# BackplaneConnector.net
KiCad netlist of a schematic drawn in Altium Designer
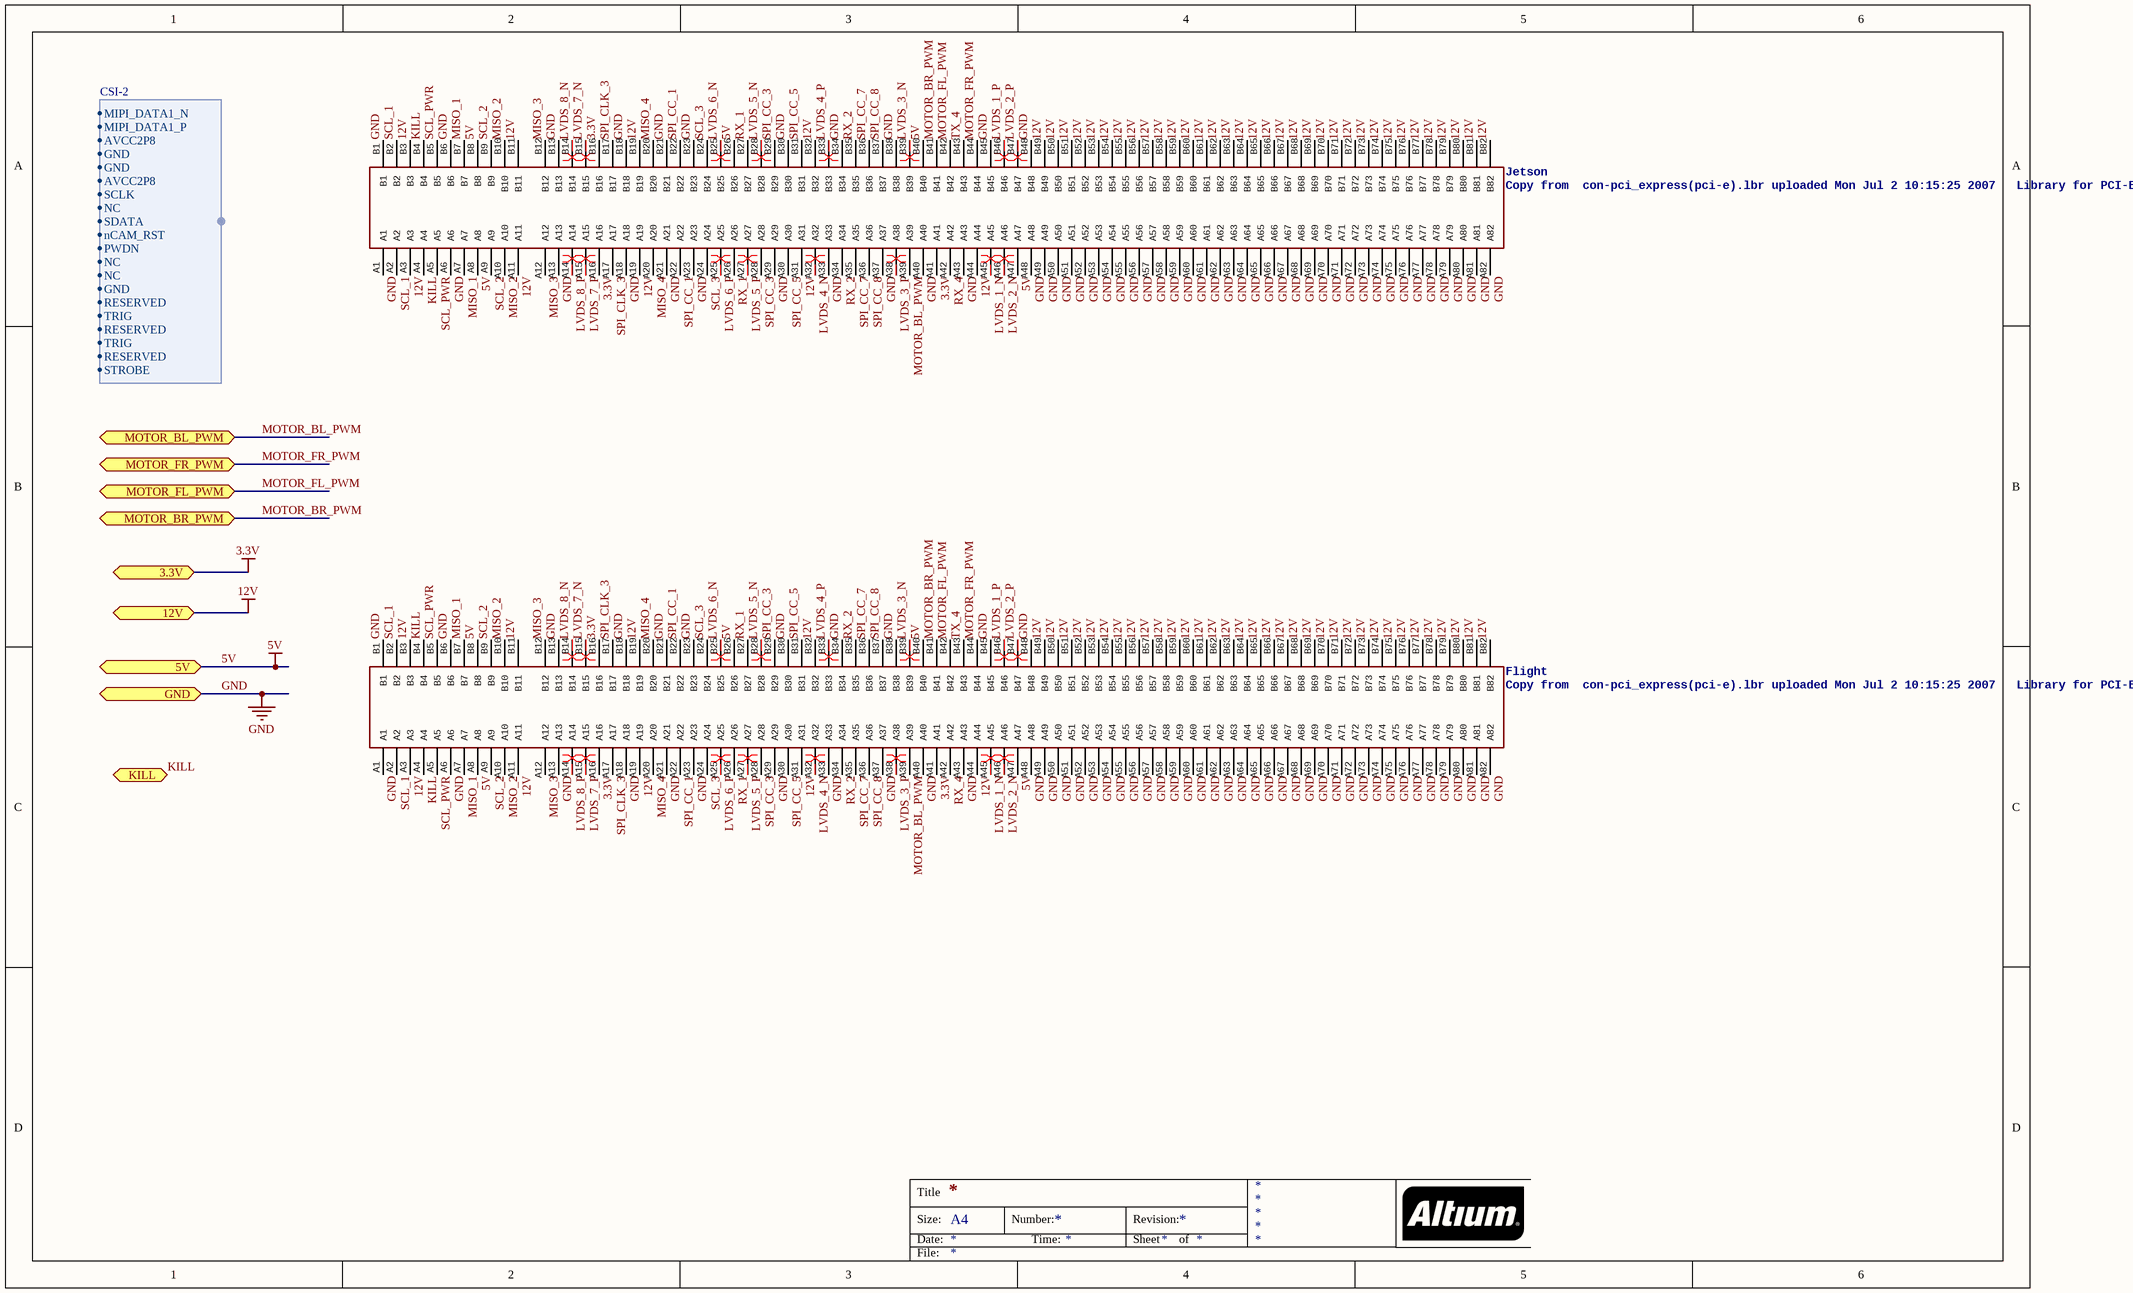
[diagram p0: BackplaneConnector.SchDoc]

(export (version "E")
  (design (tool "Eeschema 10.0.6"))
  (components
    (comp (ref "Flight")
      (value "Copy from  con-pci_express(pci-e).lbr uploaded Mon Jul 2 10:15:25 2007   Library for PCI-Express x16 (PCI-E) connector. Includes connector and card edge pattern. Uploaded by JF Duval <jfduval@aqra.ca> from AQRA.ca")
      (footprint "PCI-E-164")
      (libsource (lib "con-pc-update") (part "PCI-E-164SOCKET"))
    )
    (comp (ref "Jetson")
      (value "Copy from  con-pci_express(pci-e).lbr uploaded Mon Jul 2 10:15:25 2007   Library for PCI-Express x16 (PCI-E) connector. Includes connector and card edge pattern. Uploaded by JF Duval <jfduval@aqra.ca> from AQRA.ca")
      (footprint "PCI-E-164")
      (libsource (lib "con-pc-update") (part "PCI-E-164SOCKET"))
    )
  )
  (nets
    (net (code "1") (name "/KILL") (class "Default")
      (node (ref "Flight") (pin "A4") (pinfunction "A4_A4") (pintype "passive"))
      (node (ref "Flight") (pin "B4") (pinfunction "B4_B4") (pintype "passive"))
      (node (ref "Jetson") (pin "A4") (pinfunction "A4_A4") (pintype "passive"))
      (node (ref "Jetson") (pin "B4") (pinfunction "B4_B4") (pintype "passive"))
    )
    (net (code "2") (name "/LVDS_1_N") (class "Default")
      (node (ref "Flight") (pin "A45") (pinfunction "A45_A45") (pintype "passive"))
      (node (ref "Jetson") (pin "A45") (pinfunction "A45_A45") (pintype "passive"))
    )
    (net (code "3") (name "/LVDS_1_P") (class "Default")
      (node (ref "Flight") (pin "B46") (pinfunction "B46_B46") (pintype "passive"))
      (node (ref "Jetson") (pin "B46") (pinfunction "B46_B46") (pintype "passive"))
    )
    (net (code "4") (name "/LVDS_2_N") (class "Default")
      (node (ref "Flight") (pin "A46") (pinfunction "A46_A46") (pintype "passive"))
      (node (ref "Jetson") (pin "A46") (pinfunction "A46_A46") (pintype "passive"))
    )
    (net (code "5") (name "/LVDS_2_P") (class "Default")
      (node (ref "Flight") (pin "B47") (pinfunction "B47_B47") (pintype "passive"))
      (node (ref "Jetson") (pin "B47") (pinfunction "B47_B47") (pintype "passive"))
    )
    (net (code "6") (name "/LVDS_3_N") (class "Default")
      (node (ref "Flight") (pin "B39") (pinfunction "B39_B39") (pintype "passive"))
      (node (ref "Jetson") (pin "B39") (pinfunction "B39_B39") (pintype "passive"))
    )
    (net (code "7") (name "/LVDS_3_P") (class "Default")
      (node (ref "Flight") (pin "A38") (pinfunction "A38_A38") (pintype "passive"))
      (node (ref "Jetson") (pin "A38") (pinfunction "A38_A38") (pintype "passive"))
    )
    (net (code "8") (name "/LVDS_4_N") (class "Default")
      (node (ref "Flight") (pin "A32") (pinfunction "A32_A32") (pintype "passive"))
      (node (ref "Jetson") (pin "A32") (pinfunction "A32_A32") (pintype "passive"))
    )
    (net (code "9") (name "/LVDS_4_P") (class "Default")
      (node (ref "Flight") (pin "B33") (pinfunction "B33_B33") (pintype "passive"))
      (node (ref "Jetson") (pin "B33") (pinfunction "B33_B33") (pintype "passive"))
    )
    (net (code "10") (name "/LVDS_5_N") (class "Default")
      (node (ref "Flight") (pin "B28") (pinfunction "B28_B28") (pintype "passive"))
      (node (ref "Jetson") (pin "B28") (pinfunction "B28_B28") (pintype "passive"))
    )
    (net (code "11") (name "/LVDS_5_P") (class "Default")
      (node (ref "Flight") (pin "A27") (pinfunction "A27_A27") (pintype "passive"))
      (node (ref "Jetson") (pin "A27") (pinfunction "A27_A27") (pintype "passive"))
    )
    (net (code "12") (name "/LVDS_6_N") (class "Default")
      (node (ref "Flight") (pin "B25") (pinfunction "B25_B25") (pintype "passive"))
      (node (ref "Jetson") (pin "B25") (pinfunction "B25_B25") (pintype "passive"))
    )
    (net (code "13") (name "/LVDS_6_P") (class "Default")
      (node (ref "Flight") (pin "A25") (pinfunction "A25_A25") (pintype "passive"))
      (node (ref "Jetson") (pin "A25") (pinfunction "A25_A25") (pintype "passive"))
    )
    (net (code "14") (name "/LVDS_7_N") (class "Default")
      (node (ref "Flight") (pin "B15") (pinfunction "B15_B15") (pintype "passive"))
      (node (ref "Jetson") (pin "B15") (pinfunction "B15_B15") (pintype "passive"))
    )
    (net (code "15") (name "/LVDS_7_P") (class "Default")
      (node (ref "Flight") (pin "A15") (pinfunction "A15_A15") (pintype "passive"))
      (node (ref "Jetson") (pin "A15") (pinfunction "A15_A15") (pintype "passive"))
    )
    (net (code "16") (name "/LVDS_8_N") (class "Default")
      (node (ref "Flight") (pin "B14") (pinfunction "B14_B14") (pintype "passive"))
      (node (ref "Jetson") (pin "B14") (pinfunction "B14_B14") (pintype "passive"))
    )
    (net (code "17") (name "/LVDS_8_P") (class "Default")
      (node (ref "Flight") (pin "A14") (pinfunction "A14_A14") (pintype "passive"))
      (node (ref "Jetson") (pin "A14") (pinfunction "A14_A14") (pintype "passive"))
    )
    (net (code "18") (name "/MISO_1") (class "Default")
      (node (ref "Flight") (pin "A7") (pinfunction "A7_A7") (pintype "passive"))
      (node (ref "Flight") (pin "B7") (pinfunction "B7_B7") (pintype "passive"))
      (node (ref "Jetson") (pin "A7") (pinfunction "A7_A7") (pintype "passive"))
      (node (ref "Jetson") (pin "B7") (pinfunction "B7_B7") (pintype "passive"))
    )
    (net (code "19") (name "/MISO_2") (class "Default")
      (node (ref "Flight") (pin "A10") (pinfunction "A10_A10") (pintype "passive"))
      (node (ref "Flight") (pin "B10") (pinfunction "B10_B10") (pintype "passive"))
      (node (ref "Jetson") (pin "A10") (pinfunction "A10_A10") (pintype "passive"))
      (node (ref "Jetson") (pin "B10") (pinfunction "B10_B10") (pintype "passive"))
    )
    (net (code "20") (name "/MISO_3") (class "Default")
      (node (ref "Flight") (pin "A12") (pinfunction "A12_A12") (pintype "passive"))
      (node (ref "Flight") (pin "B12") (pinfunction "B12_B12") (pintype "passive"))
      (node (ref "Jetson") (pin "A12") (pinfunction "A12_A12") (pintype "passive"))
      (node (ref "Jetson") (pin "B12") (pinfunction "B12_B12") (pintype "passive"))
    )
    (net (code "21") (name "/MISO_4") (class "Default")
      (node (ref "Flight") (pin "A20") (pinfunction "A20_A20") (pintype "passive"))
      (node (ref "Flight") (pin "B20") (pinfunction "B20_B20") (pintype "passive"))
      (node (ref "Jetson") (pin "A20") (pinfunction "A20_A20") (pintype "passive"))
      (node (ref "Jetson") (pin "B20") (pinfunction "B20_B20") (pintype "passive"))
    )
    (net (code "22") (name "/MOTOR_BL_PWM") (class "Default")
      (node (ref "Flight") (pin "A39") (pinfunction "A39_A39") (pintype "passive"))
      (node (ref "Jetson") (pin "A39") (pinfunction "A39_A39") (pintype "passive"))
    )
    (net (code "23") (name "/MOTOR_BR_PWM") (class "Default")
      (node (ref "Flight") (pin "B41") (pinfunction "B41_B41") (pintype "passive"))
      (node (ref "Jetson") (pin "B41") (pinfunction "B41_B41") (pintype "passive"))
    )
    (net (code "24") (name "/MOTOR_FL_PWM") (class "Default")
      (node (ref "Flight") (pin "B42") (pinfunction "B42_B42") (pintype "passive"))
      (node (ref "Jetson") (pin "B42") (pinfunction "B42_B42") (pintype "passive"))
    )
    (net (code "25") (name "/MOTOR_FR_PWM") (class "Default")
      (node (ref "Flight") (pin "B44") (pinfunction "B44_B44") (pintype "passive"))
      (node (ref "Jetson") (pin "B44") (pinfunction "B44_B44") (pintype "passive"))
    )
    (net (code "26") (name "/RX_1") (class "Default")
      (node (ref "Flight") (pin "A26") (pinfunction "A26_A26") (pintype "passive"))
      (node (ref "Flight") (pin "B27") (pinfunction "B27_B27") (pintype "passive"))
      (node (ref "Jetson") (pin "A26") (pinfunction "A26_A26") (pintype "passive"))
      (node (ref "Jetson") (pin "B27") (pinfunction "B27_B27") (pintype "passive"))
    )
    (net (code "27") (name "/RX_2") (class "Default")
      (node (ref "Flight") (pin "A34") (pinfunction "A34_A34") (pintype "passive"))
      (node (ref "Flight") (pin "B35") (pinfunction "B35_B35") (pintype "passive"))
      (node (ref "Jetson") (pin "A34") (pinfunction "A34_A34") (pintype "passive"))
      (node (ref "Jetson") (pin "B35") (pinfunction "B35_B35") (pintype "passive"))
    )
    (net (code "28") (name "/RX_4") (class "Default")
      (node (ref "Flight") (pin "A42") (pinfunction "A42_A42") (pintype "passive"))
      (node (ref "Jetson") (pin "A42") (pinfunction "A42_A42") (pintype "passive"))
    )
    (net (code "29") (name "/SCL_1") (class "Default")
      (node (ref "Flight") (pin "A2") (pinfunction "A2_A2") (pintype "passive"))
      (node (ref "Flight") (pin "B2") (pinfunction "B2_B2") (pintype "passive"))
      (node (ref "Jetson") (pin "A2") (pinfunction "A2_A2") (pintype "passive"))
      (node (ref "Jetson") (pin "B2") (pinfunction "B2_B2") (pintype "passive"))
    )
    (net (code "30") (name "/SCL_2") (class "Default")
      (node (ref "Flight") (pin "A9") (pinfunction "A9_A9") (pintype "passive"))
      (node (ref "Flight") (pin "B9") (pinfunction "B9_B9") (pintype "passive"))
      (node (ref "Jetson") (pin "A9") (pinfunction "A9_A9") (pintype "passive"))
      (node (ref "Jetson") (pin "B9") (pinfunction "B9_B9") (pintype "passive"))
    )
    (net (code "31") (name "/SCL_3") (class "Default")
      (node (ref "Flight") (pin "A24") (pinfunction "A24_A24") (pintype "passive"))
      (node (ref "Flight") (pin "B24") (pinfunction "B24_B24") (pintype "passive"))
      (node (ref "Jetson") (pin "A24") (pinfunction "A24_A24") (pintype "passive"))
      (node (ref "Jetson") (pin "B24") (pinfunction "B24_B24") (pintype "passive"))
    )
    (net (code "32") (name "/SCL_PWR") (class "Default")
      (node (ref "Flight") (pin "A5") (pinfunction "A5_A5") (pintype "passive"))
      (node (ref "Flight") (pin "B5") (pinfunction "B5_B5") (pintype "passive"))
      (node (ref "Jetson") (pin "A5") (pinfunction "A5_A5") (pintype "passive"))
      (node (ref "Jetson") (pin "B5") (pinfunction "B5_B5") (pintype "passive"))
    )
    (net (code "33") (name "/SPI_CC_1") (class "Default")
      (node (ref "Flight") (pin "A22") (pinfunction "A22_A22") (pintype "passive"))
      (node (ref "Flight") (pin "B22") (pinfunction "B22_B22") (pintype "passive"))
      (node (ref "Jetson") (pin "A22") (pinfunction "A22_A22") (pintype "passive"))
      (node (ref "Jetson") (pin "B22") (pinfunction "B22_B22") (pintype "passive"))
    )
    (net (code "34") (name "/SPI_CC_3") (class "Default")
      (node (ref "Flight") (pin "A28") (pinfunction "A28_A28") (pintype "passive"))
      (node (ref "Flight") (pin "B29") (pinfunction "B29_B29") (pintype "passive"))
      (node (ref "Jetson") (pin "A28") (pinfunction "A28_A28") (pintype "passive"))
      (node (ref "Jetson") (pin "B29") (pinfunction "B29_B29") (pintype "passive"))
    )
    (net (code "35") (name "/SPI_CC_5") (class "Default")
      (node (ref "Flight") (pin "A30") (pinfunction "A30_A30") (pintype "passive"))
      (node (ref "Flight") (pin "B31") (pinfunction "B31_B31") (pintype "passive"))
      (node (ref "Jetson") (pin "A30") (pinfunction "A30_A30") (pintype "passive"))
      (node (ref "Jetson") (pin "B31") (pinfunction "B31_B31") (pintype "passive"))
    )
    (net (code "36") (name "/SPI_CC_7") (class "Default")
      (node (ref "Flight") (pin "A35") (pinfunction "A35_A35") (pintype "passive"))
      (node (ref "Flight") (pin "B36") (pinfunction "B36_B36") (pintype "passive"))
      (node (ref "Jetson") (pin "A35") (pinfunction "A35_A35") (pintype "passive"))
      (node (ref "Jetson") (pin "B36") (pinfunction "B36_B36") (pintype "passive"))
    )
    (net (code "37") (name "/SPI_CC_8") (class "Default")
      (node (ref "Flight") (pin "A36") (pinfunction "A36_A36") (pintype "passive"))
      (node (ref "Flight") (pin "B37") (pinfunction "B37_B37") (pintype "passive"))
      (node (ref "Jetson") (pin "A36") (pinfunction "A36_A36") (pintype "passive"))
      (node (ref "Jetson") (pin "B37") (pinfunction "B37_B37") (pintype "passive"))
    )
    (net (code "38") (name "/SPI_CLK_3") (class "Default")
      (node (ref "Flight") (pin "A17") (pinfunction "A17_A17") (pintype "passive"))
      (node (ref "Flight") (pin "B17") (pinfunction "B17_B17") (pintype "passive"))
      (node (ref "Jetson") (pin "A17") (pinfunction "A17_A17") (pintype "passive"))
      (node (ref "Jetson") (pin "B17") (pinfunction "B17_B17") (pintype "passive"))
    )
    (net (code "39") (name "/TX_4") (class "Default")
      (node (ref "Flight") (pin "B43") (pinfunction "B43_B43") (pintype "passive"))
      (node (ref "Jetson") (pin "B43") (pinfunction "B43_B43") (pintype "passive"))
    )
    (net (code "40") (name "3.3V") (class "Default")
      (node (ref "Flight") (pin "A16") (pinfunction "A16_A16") (pintype "passive"))
      (node (ref "Flight") (pin "A41") (pinfunction "A41_A41") (pintype "passive"))
      (node (ref "Flight") (pin "B16") (pinfunction "B16_B16") (pintype "passive"))
      (node (ref "Jetson") (pin "A16") (pinfunction "A16_A16") (pintype "passive"))
      (node (ref "Jetson") (pin "A41") (pinfunction "A41_A41") (pintype "passive"))
      (node (ref "Jetson") (pin "B16") (pinfunction "B16_B16") (pintype "passive"))
    )
    (net (code "41") (name "5V") (class "Default")
      (node (ref "Flight") (pin "A47") (pinfunction "A47_A47") (pintype "passive"))
      (node (ref "Flight") (pin "A8") (pinfunction "A8_A8") (pintype "passive"))
      (node (ref "Flight") (pin "B26") (pinfunction "B26_B26") (pintype "passive"))
      (node (ref "Flight") (pin "B40") (pinfunction "B40_B40") (pintype "passive"))
      (node (ref "Flight") (pin "B8") (pinfunction "B8_B8") (pintype "passive"))
      (node (ref "Jetson") (pin "A47") (pinfunction "A47_A47") (pintype "passive"))
      (node (ref "Jetson") (pin "A8") (pinfunction "A8_A8") (pintype "passive"))
      (node (ref "Jetson") (pin "B26") (pinfunction "B26_B26") (pintype "passive"))
      (node (ref "Jetson") (pin "B40") (pinfunction "B40_B40") (pintype "passive"))
      (node (ref "Jetson") (pin "B8") (pinfunction "B8_B8") (pintype "passive"))
    )
    (net (code "42") (name "12V") (class "Default")
      (node (ref "Flight") (pin "A11") (pinfunction "A11_A11") (pintype "passive"))
      (node (ref "Flight") (pin "A19") (pinfunction "A19_A19") (pintype "passive"))
      (node (ref "Flight") (pin "A3") (pinfunction "A3_A3") (pintype "passive"))
      (node (ref "Flight") (pin "A31") (pinfunction "A31_A31") (pintype "passive"))
      (node (ref "Flight") (pin "A44") (pinfunction "A44_A44") (pintype "passive"))
      (node (ref "Flight") (pin "B11") (pinfunction "B11_B11") (pintype "passive"))
      (node (ref "Flight") (pin "B19") (pinfunction "B19_B19") (pintype "passive"))
      (node (ref "Flight") (pin "B3") (pinfunction "B3_B3") (pintype "passive"))
      (node (ref "Flight") (pin "B32") (pinfunction "B32_B32") (pintype "passive"))
      (node (ref "Flight") (pin "B49") (pinfunction "B49_B49") (pintype "passive"))
      (node (ref "Flight") (pin "B50") (pinfunction "B50_B50") (pintype "passive"))
      (node (ref "Flight") (pin "B51") (pinfunction "B51_B51") (pintype "passive"))
      (node (ref "Flight") (pin "B52") (pinfunction "B52_B52") (pintype "passive"))
      (node (ref "Flight") (pin "B53") (pinfunction "B53_B53") (pintype "passive"))
      (node (ref "Flight") (pin "B54") (pinfunction "B54_B54") (pintype "passive"))
      (node (ref "Flight") (pin "B55") (pinfunction "B55_B55") (pintype "passive"))
      (node (ref "Flight") (pin "B56") (pinfunction "B56_B56") (pintype "passive"))
      (node (ref "Flight") (pin "B57") (pinfunction "B57_B57") (pintype "passive"))
      (node (ref "Flight") (pin "B58") (pinfunction "B58_B58") (pintype "passive"))
      (node (ref "Flight") (pin "B59") (pinfunction "B59_B59") (pintype "passive"))
      (node (ref "Flight") (pin "B60") (pinfunction "B60_B60") (pintype "passive"))
      (node (ref "Flight") (pin "B61") (pinfunction "B61_B61") (pintype "passive"))
      (node (ref "Flight") (pin "B62") (pinfunction "B62_B62") (pintype "passive"))
      (node (ref "Flight") (pin "B63") (pinfunction "B63_B63") (pintype "passive"))
      (node (ref "Flight") (pin "B64") (pinfunction "B64_B64") (pintype "passive"))
      (node (ref "Flight") (pin "B65") (pinfunction "B65_B65") (pintype "passive"))
      (node (ref "Flight") (pin "B66") (pinfunction "B66_B66") (pintype "passive"))
      (node (ref "Flight") (pin "B67") (pinfunction "B67_B67") (pintype "passive"))
      (node (ref "Flight") (pin "B68") (pinfunction "B68_B68") (pintype "passive"))
      (node (ref "Flight") (pin "B69") (pinfunction "B69_B69") (pintype "passive"))
      (node (ref "Flight") (pin "B70") (pinfunction "B70_B70") (pintype "passive"))
      (node (ref "Flight") (pin "B71") (pinfunction "B71_B71") (pintype "passive"))
      (node (ref "Flight") (pin "B72") (pinfunction "B72_B72") (pintype "passive"))
      (node (ref "Flight") (pin "B73") (pinfunction "B73_B73") (pintype "passive"))
      (node (ref "Flight") (pin "B74") (pinfunction "B74_B74") (pintype "passive"))
      (node (ref "Flight") (pin "B75") (pinfunction "B75_B75") (pintype "passive"))
      (node (ref "Flight") (pin "B76") (pinfunction "B76_B76") (pintype "passive"))
      (node (ref "Flight") (pin "B77") (pinfunction "B77_B77") (pintype "passive"))
      (node (ref "Flight") (pin "B78") (pinfunction "B78_B78") (pintype "passive"))
      (node (ref "Flight") (pin "B79") (pinfunction "B79_B79") (pintype "passive"))
      (node (ref "Flight") (pin "B80") (pinfunction "B80_B80") (pintype "passive"))
      (node (ref "Flight") (pin "B81") (pinfunction "B81_B81") (pintype "passive"))
      (node (ref "Flight") (pin "B82") (pinfunction "B82_B82") (pintype "passive"))
      (node (ref "Jetson") (pin "A11") (pinfunction "A11_A11") (pintype "passive"))
      (node (ref "Jetson") (pin "A19") (pinfunction "A19_A19") (pintype "passive"))
      (node (ref "Jetson") (pin "A3") (pinfunction "A3_A3") (pintype "passive"))
      (node (ref "Jetson") (pin "A31") (pinfunction "A31_A31") (pintype "passive"))
      (node (ref "Jetson") (pin "A44") (pinfunction "A44_A44") (pintype "passive"))
      (node (ref "Jetson") (pin "B11") (pinfunction "B11_B11") (pintype "passive"))
      (node (ref "Jetson") (pin "B19") (pinfunction "B19_B19") (pintype "passive"))
      (node (ref "Jetson") (pin "B3") (pinfunction "B3_B3") (pintype "passive"))
      (node (ref "Jetson") (pin "B32") (pinfunction "B32_B32") (pintype "passive"))
      (node (ref "Jetson") (pin "B49") (pinfunction "B49_B49") (pintype "passive"))
      (node (ref "Jetson") (pin "B50") (pinfunction "B50_B50") (pintype "passive"))
      (node (ref "Jetson") (pin "B51") (pinfunction "B51_B51") (pintype "passive"))
      (node (ref "Jetson") (pin "B52") (pinfunction "B52_B52") (pintype "passive"))
      (node (ref "Jetson") (pin "B53") (pinfunction "B53_B53") (pintype "passive"))
      (node (ref "Jetson") (pin "B54") (pinfunction "B54_B54") (pintype "passive"))
      (node (ref "Jetson") (pin "B55") (pinfunction "B55_B55") (pintype "passive"))
      (node (ref "Jetson") (pin "B56") (pinfunction "B56_B56") (pintype "passive"))
      (node (ref "Jetson") (pin "B57") (pinfunction "B57_B57") (pintype "passive"))
      (node (ref "Jetson") (pin "B58") (pinfunction "B58_B58") (pintype "passive"))
      (node (ref "Jetson") (pin "B59") (pinfunction "B59_B59") (pintype "passive"))
      (node (ref "Jetson") (pin "B60") (pinfunction "B60_B60") (pintype "passive"))
      (node (ref "Jetson") (pin "B61") (pinfunction "B61_B61") (pintype "passive"))
      (node (ref "Jetson") (pin "B62") (pinfunction "B62_B62") (pintype "passive"))
      (node (ref "Jetson") (pin "B63") (pinfunction "B63_B63") (pintype "passive"))
      (node (ref "Jetson") (pin "B64") (pinfunction "B64_B64") (pintype "passive"))
      (node (ref "Jetson") (pin "B65") (pinfunction "B65_B65") (pintype "passive"))
      (node (ref "Jetson") (pin "B66") (pinfunction "B66_B66") (pintype "passive"))
      (node (ref "Jetson") (pin "B67") (pinfunction "B67_B67") (pintype "passive"))
      (node (ref "Jetson") (pin "B68") (pinfunction "B68_B68") (pintype "passive"))
      (node (ref "Jetson") (pin "B69") (pinfunction "B69_B69") (pintype "passive"))
      (node (ref "Jetson") (pin "B70") (pinfunction "B70_B70") (pintype "passive"))
      (node (ref "Jetson") (pin "B71") (pinfunction "B71_B71") (pintype "passive"))
      (node (ref "Jetson") (pin "B72") (pinfunction "B72_B72") (pintype "passive"))
      (node (ref "Jetson") (pin "B73") (pinfunction "B73_B73") (pintype "passive"))
      (node (ref "Jetson") (pin "B74") (pinfunction "B74_B74") (pintype "passive"))
      (node (ref "Jetson") (pin "B75") (pinfunction "B75_B75") (pintype "passive"))
      (node (ref "Jetson") (pin "B76") (pinfunction "B76_B76") (pintype "passive"))
      (node (ref "Jetson") (pin "B77") (pinfunction "B77_B77") (pintype "passive"))
      (node (ref "Jetson") (pin "B78") (pinfunction "B78_B78") (pintype "passive"))
      (node (ref "Jetson") (pin "B79") (pinfunction "B79_B79") (pintype "passive"))
      (node (ref "Jetson") (pin "B80") (pinfunction "B80_B80") (pintype "passive"))
      (node (ref "Jetson") (pin "B81") (pinfunction "B81_B81") (pintype "passive"))
      (node (ref "Jetson") (pin "B82") (pinfunction "B82_B82") (pintype "passive"))
    )
    (net (code "43") (name "GND") (class "Default")
      (node (ref "Flight") (pin "A1") (pinfunction "A1_A1") (pintype "passive"))
      (node (ref "Flight") (pin "A13") (pinfunction "A13_A13") (pintype "passive"))
      (node (ref "Flight") (pin "A18") (pinfunction "A18_A18") (pintype "passive"))
      (node (ref "Flight") (pin "A21") (pinfunction "A21_A21") (pintype "passive"))
      (node (ref "Flight") (pin "A23") (pinfunction "A23_A23") (pintype "passive"))
      (node (ref "Flight") (pin "A29") (pinfunction "A29_A29") (pintype "passive"))
      (node (ref "Flight") (pin "A33") (pinfunction "A33_A33") (pintype "passive"))
      (node (ref "Flight") (pin "A37") (pinfunction "A37_A37") (pintype "passive"))
      (node (ref "Flight") (pin "A40") (pinfunction "A40_A40") (pintype "passive"))
      (node (ref "Flight") (pin "A43") (pinfunction "A43_A43") (pintype "passive"))
      (node (ref "Flight") (pin "A48") (pinfunction "A48_A48") (pintype "passive"))
      (node (ref "Flight") (pin "A49") (pinfunction "A49_A49") (pintype "passive"))
      (node (ref "Flight") (pin "A50") (pinfunction "A50_A50") (pintype "passive"))
      (node (ref "Flight") (pin "A51") (pinfunction "A51_A51") (pintype "passive"))
      (node (ref "Flight") (pin "A52") (pinfunction "A52_A52") (pintype "passive"))
      (node (ref "Flight") (pin "A53") (pinfunction "A53_A53") (pintype "passive"))
      (node (ref "Flight") (pin "A54") (pinfunction "A54_A54") (pintype "passive"))
      (node (ref "Flight") (pin "A55") (pinfunction "A55_A55") (pintype "passive"))
      (node (ref "Flight") (pin "A56") (pinfunction "A56_A56") (pintype "passive"))
      (node (ref "Flight") (pin "A57") (pinfunction "A57_A57") (pintype "passive"))
      (node (ref "Flight") (pin "A58") (pinfunction "A58_A58") (pintype "passive"))
      (node (ref "Flight") (pin "A59") (pinfunction "A59_A59") (pintype "passive"))
      (node (ref "Flight") (pin "A6") (pinfunction "A6_A6") (pintype "passive"))
      (node (ref "Flight") (pin "A60") (pinfunction "A60_A60") (pintype "passive"))
      (node (ref "Flight") (pin "A61") (pinfunction "A61_A61") (pintype "passive"))
      (node (ref "Flight") (pin "A62") (pinfunction "A62_A62") (pintype "passive"))
      (node (ref "Flight") (pin "A63") (pinfunction "A63_A63") (pintype "passive"))
      (node (ref "Flight") (pin "A64") (pinfunction "A64_A64") (pintype "passive"))
      (node (ref "Flight") (pin "A65") (pinfunction "A65_A65") (pintype "passive"))
      (node (ref "Flight") (pin "A66") (pinfunction "A66_A66") (pintype "passive"))
      (node (ref "Flight") (pin "A67") (pinfunction "A67_A67") (pintype "passive"))
      (node (ref "Flight") (pin "A68") (pinfunction "A68_A68") (pintype "passive"))
      (node (ref "Flight") (pin "A69") (pinfunction "A69_A69") (pintype "passive"))
      (node (ref "Flight") (pin "A70") (pinfunction "A70_A70") (pintype "passive"))
      (node (ref "Flight") (pin "A71") (pinfunction "A71_A71") (pintype "passive"))
      (node (ref "Flight") (pin "A72") (pinfunction "A72_A72") (pintype "passive"))
      (node (ref "Flight") (pin "A73") (pinfunction "A73_A73") (pintype "passive"))
      (node (ref "Flight") (pin "A74") (pinfunction "A74_A74") (pintype "passive"))
      (node (ref "Flight") (pin "A75") (pinfunction "A75_A75") (pintype "passive"))
      (node (ref "Flight") (pin "A76") (pinfunction "A76_A76") (pintype "passive"))
      (node (ref "Flight") (pin "A77") (pinfunction "A77_A77") (pintype "passive"))
      (node (ref "Flight") (pin "A78") (pinfunction "A78_A78") (pintype "passive"))
      (node (ref "Flight") (pin "A79") (pinfunction "A79_A79") (pintype "passive"))
      (node (ref "Flight") (pin "A80") (pinfunction "A80_A80") (pintype "passive"))
      (node (ref "Flight") (pin "A81") (pinfunction "A81_A81") (pintype "passive"))
      (node (ref "Flight") (pin "A82") (pinfunction "A82_A82") (pintype "passive"))
      (node (ref "Flight") (pin "B1") (pinfunction "B1_B1") (pintype "passive"))
      (node (ref "Flight") (pin "B13") (pinfunction "B13_B13") (pintype "passive"))
      (node (ref "Flight") (pin "B18") (pinfunction "B18_B18") (pintype "passive"))
      (node (ref "Flight") (pin "B21") (pinfunction "B21_B21") (pintype "passive"))
      (node (ref "Flight") (pin "B23") (pinfunction "B23_B23") (pintype "passive"))
      (node (ref "Flight") (pin "B30") (pinfunction "B30_B30") (pintype "passive"))
      (node (ref "Flight") (pin "B34") (pinfunction "B34_B34") (pintype "passive"))
      (node (ref "Flight") (pin "B38") (pinfunction "B38_B38") (pintype "passive"))
      (node (ref "Flight") (pin "B45") (pinfunction "B45_B45") (pintype "passive"))
      (node (ref "Flight") (pin "B48") (pinfunction "B48_B48") (pintype "passive"))
      (node (ref "Flight") (pin "B6") (pinfunction "B6_B6") (pintype "passive"))
      (node (ref "Jetson") (pin "A1") (pinfunction "A1_A1") (pintype "passive"))
      (node (ref "Jetson") (pin "A13") (pinfunction "A13_A13") (pintype "passive"))
      (node (ref "Jetson") (pin "A18") (pinfunction "A18_A18") (pintype "passive"))
      (node (ref "Jetson") (pin "A21") (pinfunction "A21_A21") (pintype "passive"))
      (node (ref "Jetson") (pin "A23") (pinfunction "A23_A23") (pintype "passive"))
      (node (ref "Jetson") (pin "A29") (pinfunction "A29_A29") (pintype "passive"))
      (node (ref "Jetson") (pin "A33") (pinfunction "A33_A33") (pintype "passive"))
      (node (ref "Jetson") (pin "A37") (pinfunction "A37_A37") (pintype "passive"))
      (node (ref "Jetson") (pin "A40") (pinfunction "A40_A40") (pintype "passive"))
      (node (ref "Jetson") (pin "A43") (pinfunction "A43_A43") (pintype "passive"))
      (node (ref "Jetson") (pin "A48") (pinfunction "A48_A48") (pintype "passive"))
      (node (ref "Jetson") (pin "A49") (pinfunction "A49_A49") (pintype "passive"))
      (node (ref "Jetson") (pin "A50") (pinfunction "A50_A50") (pintype "passive"))
      (node (ref "Jetson") (pin "A51") (pinfunction "A51_A51") (pintype "passive"))
      (node (ref "Jetson") (pin "A52") (pinfunction "A52_A52") (pintype "passive"))
      (node (ref "Jetson") (pin "A53") (pinfunction "A53_A53") (pintype "passive"))
      (node (ref "Jetson") (pin "A54") (pinfunction "A54_A54") (pintype "passive"))
      (node (ref "Jetson") (pin "A55") (pinfunction "A55_A55") (pintype "passive"))
      (node (ref "Jetson") (pin "A56") (pinfunction "A56_A56") (pintype "passive"))
      (node (ref "Jetson") (pin "A57") (pinfunction "A57_A57") (pintype "passive"))
      (node (ref "Jetson") (pin "A58") (pinfunction "A58_A58") (pintype "passive"))
      (node (ref "Jetson") (pin "A59") (pinfunction "A59_A59") (pintype "passive"))
      (node (ref "Jetson") (pin "A6") (pinfunction "A6_A6") (pintype "passive"))
      (node (ref "Jetson") (pin "A60") (pinfunction "A60_A60") (pintype "passive"))
      (node (ref "Jetson") (pin "A61") (pinfunction "A61_A61") (pintype "passive"))
      (node (ref "Jetson") (pin "A62") (pinfunction "A62_A62") (pintype "passive"))
      (node (ref "Jetson") (pin "A63") (pinfunction "A63_A63") (pintype "passive"))
      (node (ref "Jetson") (pin "A64") (pinfunction "A64_A64") (pintype "passive"))
      (node (ref "Jetson") (pin "A65") (pinfunction "A65_A65") (pintype "passive"))
      (node (ref "Jetson") (pin "A66") (pinfunction "A66_A66") (pintype "passive"))
      (node (ref "Jetson") (pin "A67") (pinfunction "A67_A67") (pintype "passive"))
      (node (ref "Jetson") (pin "A68") (pinfunction "A68_A68") (pintype "passive"))
      (node (ref "Jetson") (pin "A69") (pinfunction "A69_A69") (pintype "passive"))
      (node (ref "Jetson") (pin "A70") (pinfunction "A70_A70") (pintype "passive"))
      (node (ref "Jetson") (pin "A71") (pinfunction "A71_A71") (pintype "passive"))
      (node (ref "Jetson") (pin "A72") (pinfunction "A72_A72") (pintype "passive"))
      (node (ref "Jetson") (pin "A73") (pinfunction "A73_A73") (pintype "passive"))
      (node (ref "Jetson") (pin "A74") (pinfunction "A74_A74") (pintype "passive"))
      (node (ref "Jetson") (pin "A75") (pinfunction "A75_A75") (pintype "passive"))
      (node (ref "Jetson") (pin "A76") (pinfunction "A76_A76") (pintype "passive"))
      (node (ref "Jetson") (pin "A77") (pinfunction "A77_A77") (pintype "passive"))
      (node (ref "Jetson") (pin "A78") (pinfunction "A78_A78") (pintype "passive"))
      (node (ref "Jetson") (pin "A79") (pinfunction "A79_A79") (pintype "passive"))
      (node (ref "Jetson") (pin "A80") (pinfunction "A80_A80") (pintype "passive"))
      (node (ref "Jetson") (pin "A81") (pinfunction "A81_A81") (pintype "passive"))
      (node (ref "Jetson") (pin "A82") (pinfunction "A82_A82") (pintype "passive"))
      (node (ref "Jetson") (pin "B1") (pinfunction "B1_B1") (pintype "passive"))
      (node (ref "Jetson") (pin "B13") (pinfunction "B13_B13") (pintype "passive"))
      (node (ref "Jetson") (pin "B18") (pinfunction "B18_B18") (pintype "passive"))
      (node (ref "Jetson") (pin "B21") (pinfunction "B21_B21") (pintype "passive"))
      (node (ref "Jetson") (pin "B23") (pinfunction "B23_B23") (pintype "passive"))
      (node (ref "Jetson") (pin "B30") (pinfunction "B30_B30") (pintype "passive"))
      (node (ref "Jetson") (pin "B34") (pinfunction "B34_B34") (pintype "passive"))
      (node (ref "Jetson") (pin "B38") (pinfunction "B38_B38") (pintype "passive"))
      (node (ref "Jetson") (pin "B45") (pinfunction "B45_B45") (pintype "passive"))
      (node (ref "Jetson") (pin "B48") (pinfunction "B48_B48") (pintype "passive"))
      (node (ref "Jetson") (pin "B6") (pinfunction "B6_B6") (pintype "passive"))
    )
  )
)
